# DoorModule_V2_0.net
KiCad netlist of a schematic drawn in EAGLE
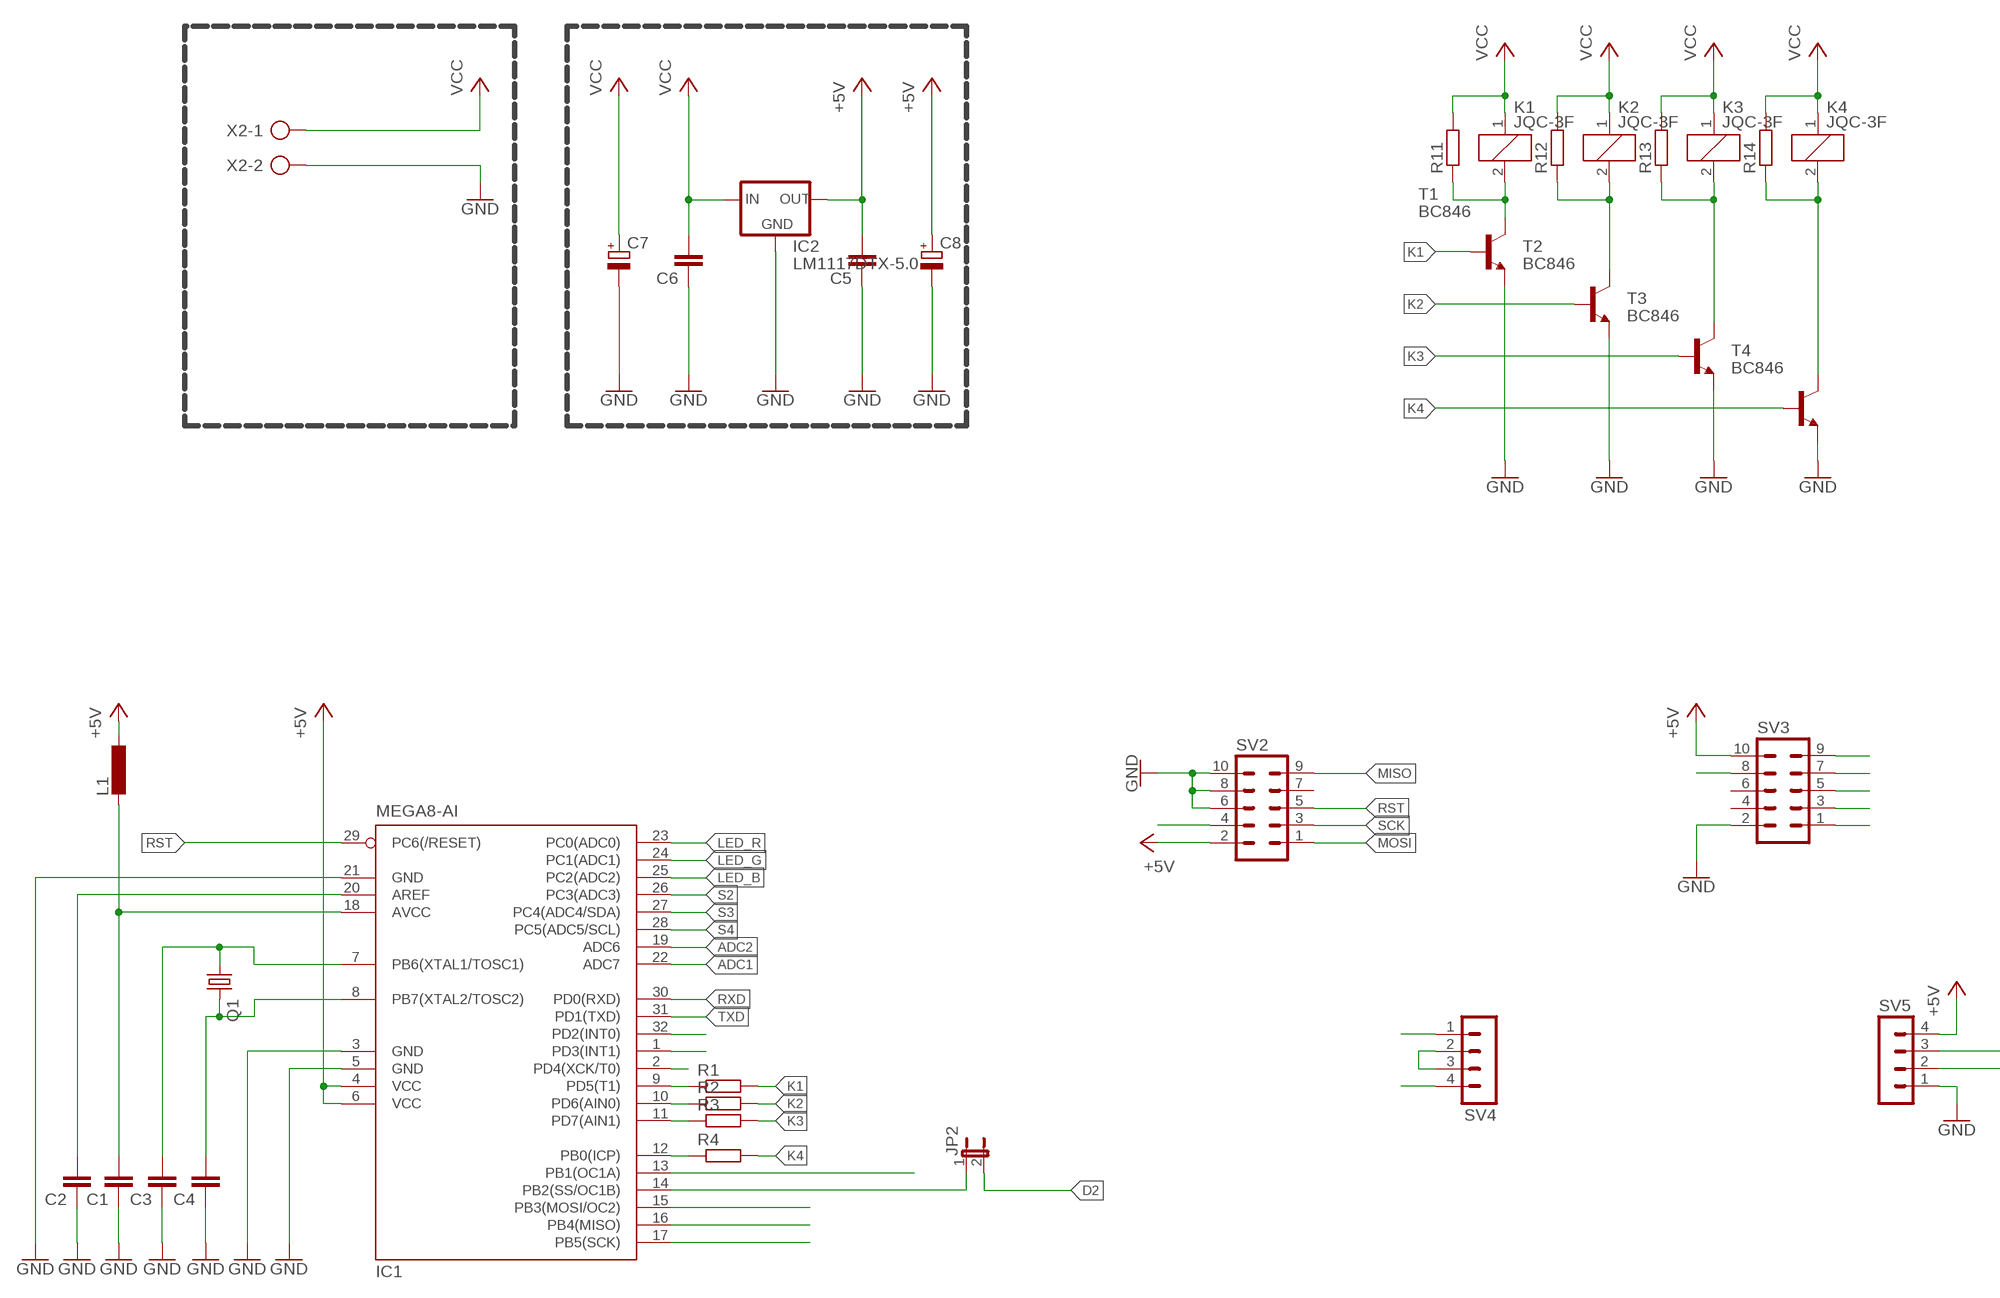
[diagram p0: schematic, sheet 1, part 1 of 2]
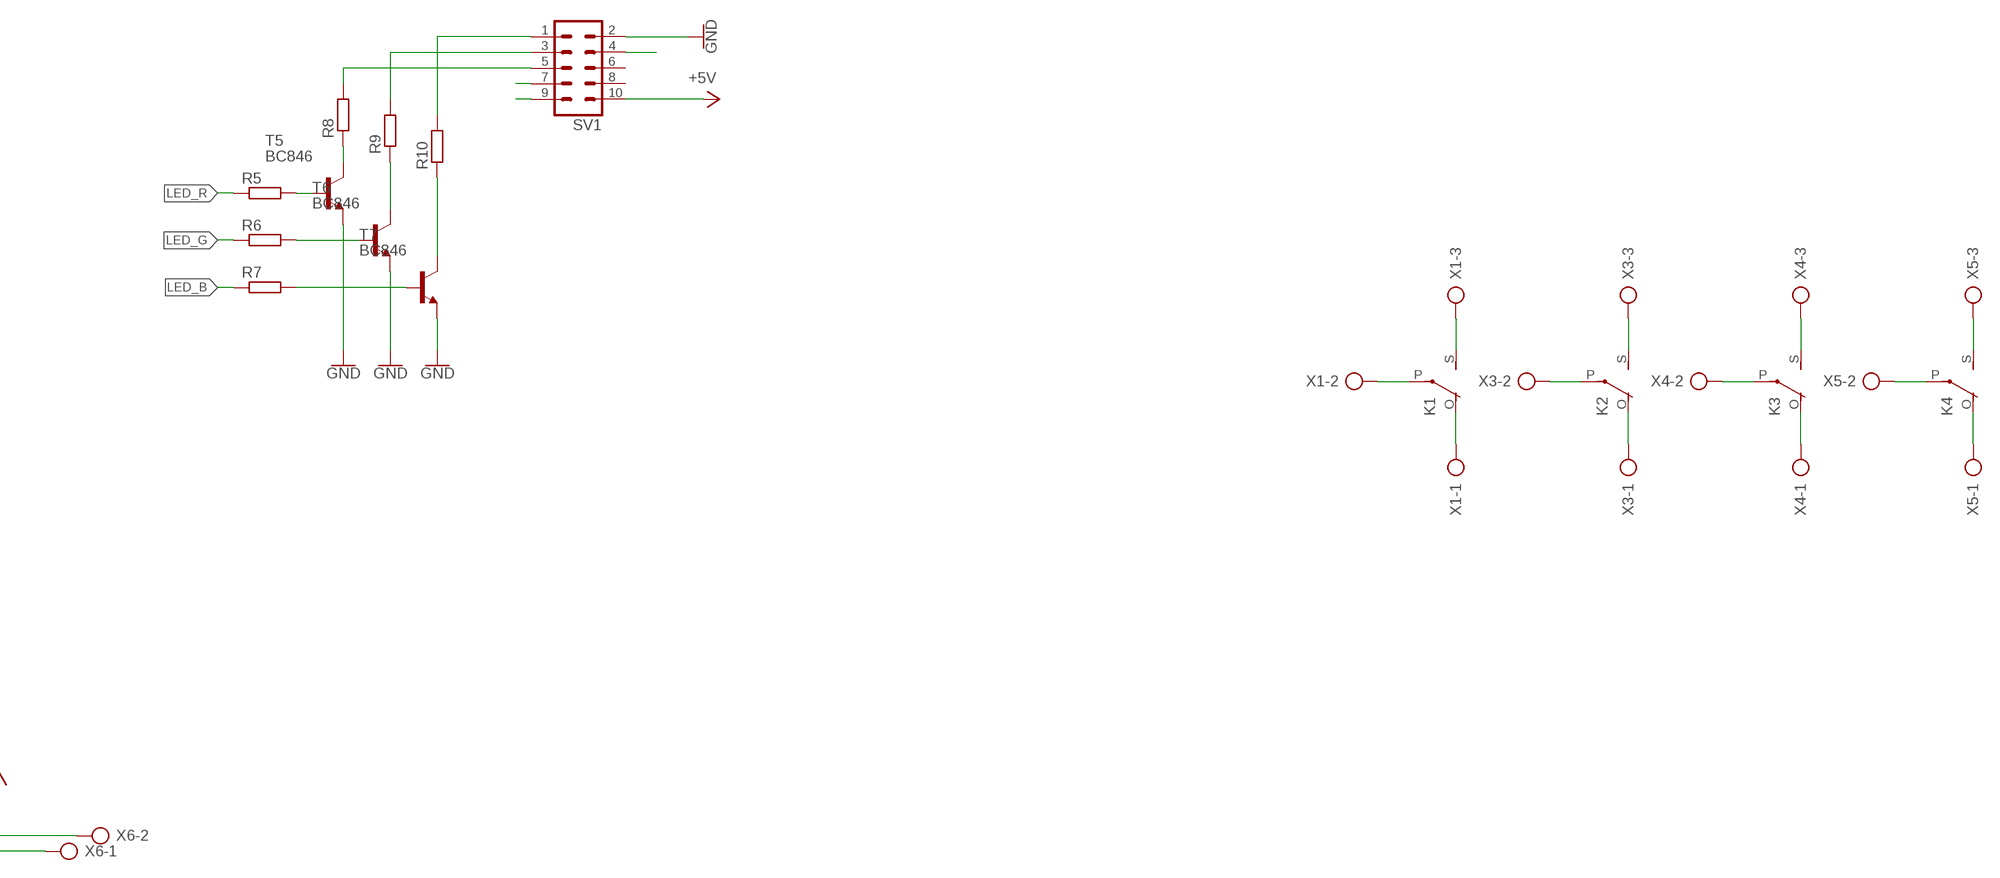
[diagram p1: schematic, sheet 1, part 2 of 2]

(export (version "E")
  (design (tool "Eeschema 10.0.6"))
  (components
    (comp (ref "C1")
      (value "C-EUC0805")
      (footprint "eagle-import:C0805")
      (libsource (lib "eagle-import") (part "C-EUC0805"))
    )
    (comp (ref "C2")
      (value "C-EUC0805")
      (footprint "eagle-import:C0805")
      (libsource (lib "eagle-import") (part "C-EUC0805"))
    )
    (comp (ref "C3")
      (value "C-EUC0805")
      (footprint "eagle-import:C0805")
      (libsource (lib "eagle-import") (part "C-EUC0805"))
    )
    (comp (ref "C4")
      (value "C-EUC0805")
      (footprint "eagle-import:C0805")
      (libsource (lib "eagle-import") (part "C-EUC0805"))
    )
    (comp (ref "C5")
      (value "C-EUC0805")
      (footprint "eagle-import:C0805")
      (libsource (lib "eagle-import") (part "C-EUC0805"))
    )
    (comp (ref "C6")
      (value "C-EUC0805")
      (footprint "eagle-import:C0805")
      (libsource (lib "eagle-import") (part "C-EUC0805"))
    )
    (comp (ref "C7")
      (value "CPOL-EUE2.5-7")
      (footprint "eagle-import:E2,5-7")
      (libsource (lib "eagle-import") (part "CPOL-EUE2.5-7"))
    )
    (comp (ref "C8")
      (value "CPOL-EUE2.5-7")
      (footprint "eagle-import:E2,5-7")
      (libsource (lib "eagle-import") (part "CPOL-EUE2.5-7"))
    )
    (comp (ref "IC1")
      (value "MEGA8-AI")
      (footprint "eagle-import:TQFP32-08")
      (fields (field (name "MPN") "ATMEGA8-16AU"))
      (libsource (lib "eagle-import") (part "MEGA8-AI"))
    )
    (comp (ref "IC2")
      (value "LM1117DTX-5.0")
      (footprint "eagle-import:TO252")
      (libsource (lib "eagle-import") (part "LM1117DTX-5.0"))
    )
    (comp (ref "JP2")
      (value "JP1E")
      (footprint "eagle-import:JP1")
      (libsource (lib "eagle-import") (part "JP1E"))
    )
    (comp (ref "K1")
      (value "JQC-3F")
      (footprint "eagle-import:G5LE")
      (libsource (lib "eagle-import") (part "G5LE"))
    )
    (comp (ref "K2")
      (value "JQC-3F")
      (footprint "eagle-import:G5LE")
      (libsource (lib "eagle-import") (part "G5LE"))
    )
    (comp (ref "K3")
      (value "JQC-3F")
      (footprint "eagle-import:G5LE")
      (libsource (lib "eagle-import") (part "G5LE"))
    )
    (comp (ref "K4")
      (value "JQC-3F")
      (footprint "eagle-import:G5LE")
      (libsource (lib "eagle-import") (part "G5LE"))
    )
    (comp (ref "L1")
      (value "L-EU0204/7")
      (footprint "eagle-import:0204_7")
      (libsource (lib "eagle-import") (part "L-EU0204/7"))
    )
    (comp (ref "Q1")
      (value "CRYSTALHC49U-V")
      (footprint "eagle-import:HC49U-V")
      (libsource (lib "eagle-import") (part "CRYSTALHC49U-V"))
    )
    (comp (ref "R1")
      (value "R-EU_R0805")
      (footprint "eagle-import:R0805")
      (libsource (lib "eagle-import") (part "R-EU_R0805"))
    )
    (comp (ref "R2")
      (value "R-EU_R0805")
      (footprint "eagle-import:R0805")
      (libsource (lib "eagle-import") (part "R-EU_R0805"))
    )
    (comp (ref "R3")
      (value "R-EU_R0805")
      (footprint "eagle-import:R0805")
      (libsource (lib "eagle-import") (part "R-EU_R0805"))
    )
    (comp (ref "R4")
      (value "R-EU_R0805")
      (footprint "eagle-import:R0805")
      (libsource (lib "eagle-import") (part "R-EU_R0805"))
    )
    (comp (ref "R5")
      (value "R-EU_R0805")
      (footprint "eagle-import:R0805")
      (libsource (lib "eagle-import") (part "R-EU_R0805"))
    )
    (comp (ref "R6")
      (value "R-EU_R0805")
      (footprint "eagle-import:R0805")
      (libsource (lib "eagle-import") (part "R-EU_R0805"))
    )
    (comp (ref "R7")
      (value "R-EU_R0805")
      (footprint "eagle-import:R0805")
      (libsource (lib "eagle-import") (part "R-EU_R0805"))
    )
    (comp (ref "R8")
      (value "R-EU_0204/7")
      (footprint "eagle-import:0204_7")
      (libsource (lib "eagle-import") (part "R-EU_0204/7"))
    )
    (comp (ref "R9")
      (value "R-EU_0204/7")
      (footprint "eagle-import:0204_7")
      (libsource (lib "eagle-import") (part "R-EU_0204/7"))
    )
    (comp (ref "R10")
      (value "R-EU_R0805")
      (footprint "eagle-import:R0805")
      (libsource (lib "eagle-import") (part "R-EU_R0805"))
    )
    (comp (ref "R11")
      (value "R-EU_R0805")
      (footprint "eagle-import:R0805")
      (libsource (lib "eagle-import") (part "R-EU_R0805"))
    )
    (comp (ref "R12")
      (value "R-EU_R0805")
      (footprint "eagle-import:R0805")
      (libsource (lib "eagle-import") (part "R-EU_R0805"))
    )
    (comp (ref "R13")
      (value "R-EU_R0805")
      (footprint "eagle-import:R0805")
      (libsource (lib "eagle-import") (part "R-EU_R0805"))
    )
    (comp (ref "R14")
      (value "R-EU_R0805")
      (footprint "eagle-import:R0805")
      (libsource (lib "eagle-import") (part "R-EU_R0805"))
    )
    (comp (ref "SV1")
      (value "ML10L")
      (footprint "eagle-import:ML10L")
      (libsource (lib "eagle-import") (part "ML10L"))
    )
    (comp (ref "SV2")
      (value "ML10L")
      (footprint "eagle-import:ML10L")
      (libsource (lib "eagle-import") (part "ML10L"))
    )
    (comp (ref "SV3")
      (value "ML10L")
      (footprint "eagle-import:ML10L")
      (libsource (lib "eagle-import") (part "ML10L"))
    )
    (comp (ref "SV4")
      (value "MA04-1")
      (footprint "eagle-import:MA04-1")
      (libsource (lib "eagle-import") (part "MA04-1"))
    )
    (comp (ref "SV5")
      (value "MA04-1")
      (footprint "eagle-import:MA04-1")
      (libsource (lib "eagle-import") (part "MA04-1"))
    )
    (comp (ref "T1")
      (value "BC846")
      (footprint "eagle-import:SOT23")
      (libsource (lib "eagle-import") (part "BC846"))
    )
    (comp (ref "T2")
      (value "BC846")
      (footprint "eagle-import:SOT23")
      (libsource (lib "eagle-import") (part "BC846"))
    )
    (comp (ref "T3")
      (value "BC846")
      (footprint "eagle-import:SOT23")
      (libsource (lib "eagle-import") (part "BC846"))
    )
    (comp (ref "T4")
      (value "BC846")
      (footprint "eagle-import:SOT23")
      (libsource (lib "eagle-import") (part "BC846"))
    )
    (comp (ref "T5")
      (value "BC846")
      (footprint "eagle-import:SOT23")
      (libsource (lib "eagle-import") (part "BC846"))
    )
    (comp (ref "T6")
      (value "BC846")
      (footprint "eagle-import:SOT23")
      (libsource (lib "eagle-import") (part "BC846"))
    )
    (comp (ref "T7")
      (value "BC846")
      (footprint "eagle-import:SOT23")
      (libsource (lib "eagle-import") (part "BC846"))
    )
    (comp (ref "X1")
      (value "AK300/3")
      (footprint "eagle-import:AK300_3")
      (libsource (lib "eagle-import") (part "AK300/3"))
    )
    (comp (ref "X2")
      (value "AK300/2")
      (footprint "eagle-import:AK300_2")
      (libsource (lib "eagle-import") (part "AK300/2"))
    )
    (comp (ref "X3")
      (value "AK300/3")
      (footprint "eagle-import:AK300_3")
      (libsource (lib "eagle-import") (part "AK300/3"))
    )
    (comp (ref "X4")
      (value "AK300/3")
      (footprint "eagle-import:AK300_3")
      (libsource (lib "eagle-import") (part "AK300/3"))
    )
    (comp (ref "X5")
      (value "AK300/3")
      (footprint "eagle-import:AK300_3")
      (libsource (lib "eagle-import") (part "AK300/3"))
    )
    (comp (ref "X6")
      (value "AK300/2")
      (footprint "eagle-import:AK300_2")
      (libsource (lib "eagle-import") (part "AK300/2"))
    )
  )
  (nets
    (net (code "1") (name "+5V") (class "Default")
      (node (ref "C5") (pin "2") (pinfunction "2_2") (pintype "passive"))
      (node (ref "C8") (pin "+") (pinfunction "+_+") (pintype "passive"))
      (node (ref "IC1") (pin "4") (pinfunction "VCC_4") (pintype "power_in"))
      (node (ref "IC1") (pin "6") (pinfunction "VCC_6") (pintype "power_in"))
      (node (ref "IC2") (pin "TAB") (pinfunction "OUT_TAB") (pintype "passive"))
      (node (ref "L1") (pin "1") (pinfunction "1_1") (pintype "passive"))
      (node (ref "SV1") (pin "10") (pinfunction "10_10") (pintype "passive"))
      (node (ref "SV2") (pin "2") (pinfunction "2_2") (pintype "passive"))
      (node (ref "SV3") (pin "10") (pinfunction "10_10") (pintype "passive"))
      (node (ref "SV5") (pin "4") (pinfunction "4_4") (pintype "passive"))
    )
    (net (code "2") (name "/D1") (class "Default")
      (node (ref "IC1") (pin "13") (pinfunction "PB1(OC1A)_13") (pintype "bidirectional"))
      (node (ref "SV1") (pin "4") (pinfunction "4_4") (pintype "passive"))
    )
    (net (code "3") (name "/INT0") (class "Default")
      (node (ref "IC1") (pin "32") (pinfunction "PD2(INT0)_32") (pintype "bidirectional"))
      (node (ref "SV3") (pin "9") (pinfunction "9_9") (pintype "passive"))
    )
    (net (code "4") (name "/INT1") (class "Default")
      (node (ref "IC1") (pin "1") (pinfunction "PD3(INT1)_1") (pintype "bidirectional"))
      (node (ref "SV3") (pin "8") (pinfunction "8_8") (pintype "passive"))
    )
    (net (code "5") (name "/RS") (class "Default")
      (node (ref "IC1") (pin "2") (pinfunction "PD4(XCK/T0)_2") (pintype "bidirectional"))
      (node (ref "SV4") (pin "2") (pinfunction "2_2") (pintype "passive"))
      (node (ref "SV4") (pin "3") (pinfunction "3_3") (pintype "passive"))
    )
    (net (code "6") (name "ADC1") (class "Default")
      (node (ref "IC1") (pin "22") (pinfunction "ADC7_22") (pintype "bidirectional"))
      (node (ref "SV3") (pin "1") (pinfunction "1_1") (pintype "passive"))
    )
    (net (code "7") (name "ADC2") (class "Default")
      (node (ref "IC1") (pin "19") (pinfunction "ADC6_19") (pintype "bidirectional"))
      (node (ref "SV3") (pin "3") (pinfunction "3_3") (pintype "passive"))
    )
    (net (code "8") (name "D2") (class "Default")
      (node (ref "JP2") (pin "2") (pinfunction "2_2") (pintype "passive"))
      (node (ref "SV2") (pin "4") (pinfunction "4_4") (pintype "passive"))
    )
    (net (code "9") (name "GND") (class "Default")
      (node (ref "C1") (pin "1") (pinfunction "1_1") (pintype "passive"))
      (node (ref "C2") (pin "1") (pinfunction "1_1") (pintype "passive"))
      (node (ref "C3") (pin "1") (pinfunction "1_1") (pintype "passive"))
      (node (ref "C4") (pin "1") (pinfunction "1_1") (pintype "passive"))
      (node (ref "C5") (pin "1") (pinfunction "1_1") (pintype "passive"))
      (node (ref "C6") (pin "1") (pinfunction "1_1") (pintype "passive"))
      (node (ref "C7") (pin "-") (pinfunction "-_-") (pintype "passive"))
      (node (ref "C8") (pin "-") (pinfunction "-_-") (pintype "passive"))
      (node (ref "IC1") (pin "21") (pinfunction "GND_21") (pintype "power_in"))
      (node (ref "IC1") (pin "3") (pinfunction "GND_3") (pintype "power_in"))
      (node (ref "IC1") (pin "5") (pinfunction "GND_5") (pintype "power_in"))
      (node (ref "IC2") (pin "1") (pinfunction "GND_1") (pintype "input"))
      (node (ref "SV1") (pin "2") (pinfunction "2_2") (pintype "passive"))
      (node (ref "SV2") (pin "10") (pinfunction "10_10") (pintype "passive"))
      (node (ref "SV2") (pin "6") (pinfunction "6_6") (pintype "passive"))
      (node (ref "SV2") (pin "8") (pinfunction "8_8") (pintype "passive"))
      (node (ref "SV3") (pin "2") (pinfunction "2_2") (pintype "passive"))
      (node (ref "SV5") (pin "1") (pinfunction "1_1") (pintype "passive"))
      (node (ref "T1") (pin "2") (pinfunction "E_2") (pintype "passive"))
      (node (ref "T2") (pin "2") (pinfunction "E_2") (pintype "passive"))
      (node (ref "T3") (pin "2") (pinfunction "E_2") (pintype "passive"))
      (node (ref "T4") (pin "2") (pinfunction "E_2") (pintype "passive"))
      (node (ref "T5") (pin "2") (pinfunction "E_2") (pintype "passive"))
      (node (ref "T6") (pin "2") (pinfunction "E_2") (pintype "passive"))
      (node (ref "T7") (pin "2") (pinfunction "E_2") (pintype "passive"))
      (node (ref "X2") (pin "2") (pinfunction "KL_2") (pintype "passive"))
    )
    (net (code "10") (name "K1") (class "Default")
      (node (ref "R1") (pin "2") (pinfunction "2_2") (pintype "passive"))
      (node (ref "T1") (pin "1") (pinfunction "B_1") (pintype "passive"))
    )
    (net (code "11") (name "K2") (class "Default")
      (node (ref "R2") (pin "2") (pinfunction "2_2") (pintype "passive"))
      (node (ref "T2") (pin "1") (pinfunction "B_1") (pintype "passive"))
    )
    (net (code "12") (name "K3") (class "Default")
      (node (ref "R3") (pin "2") (pinfunction "2_2") (pintype "passive"))
      (node (ref "T3") (pin "1") (pinfunction "B_1") (pintype "passive"))
    )
    (net (code "13") (name "K4") (class "Default")
      (node (ref "R4") (pin "2") (pinfunction "2_2") (pintype "passive"))
      (node (ref "T4") (pin "1") (pinfunction "B_1") (pintype "passive"))
    )
    (net (code "14") (name "LED_B") (class "Default")
      (node (ref "IC1") (pin "25") (pinfunction "PC2(ADC2)_25") (pintype "bidirectional"))
      (node (ref "R7") (pin "1") (pinfunction "1_1") (pintype "passive"))
    )
    (net (code "15") (name "LED_G") (class "Default")
      (node (ref "IC1") (pin "24") (pinfunction "PC1(ADC1)_24") (pintype "bidirectional"))
      (node (ref "R6") (pin "1") (pinfunction "1_1") (pintype "passive"))
    )
    (net (code "16") (name "LED_R") (class "Default")
      (node (ref "IC1") (pin "23") (pinfunction "PC0(ADC0)_23") (pintype "bidirectional"))
      (node (ref "R5") (pin "1") (pinfunction "1_1") (pintype "passive"))
    )
    (net (code "17") (name "MISO") (class "Default")
      (node (ref "IC1") (pin "16") (pinfunction "PB4(MISO)_16") (pintype "bidirectional"))
      (node (ref "SV2") (pin "9") (pinfunction "9_9") (pintype "passive"))
    )
    (net (code "18") (name "MOSI") (class "Default")
      (node (ref "IC1") (pin "15") (pinfunction "PB3(MOSI/OC2)_15") (pintype "bidirectional"))
      (node (ref "SV2") (pin "1") (pinfunction "1_1") (pintype "passive"))
    )
    (net (code "19") (name "Net-(IC1-AREF)") (class "Default")
      (node (ref "C2") (pin "2") (pinfunction "2_2") (pintype "passive"))
      (node (ref "IC1") (pin "20") (pinfunction "AREF_20") (pintype "passive"))
    )
    (net (code "20") (name "Net-(IC1-AVCC)") (class "Default")
      (node (ref "C1") (pin "2") (pinfunction "2_2") (pintype "passive"))
      (node (ref "IC1") (pin "18") (pinfunction "AVCC_18") (pintype "power_in"))
      (node (ref "L1") (pin "2") (pinfunction "2_2") (pintype "passive"))
    )
    (net (code "21") (name "Net-(IC1-PB0(ICP))") (class "Default")
      (node (ref "IC1") (pin "12") (pinfunction "PB0(ICP)_12") (pintype "bidirectional"))
      (node (ref "R4") (pin "1") (pinfunction "1_1") (pintype "passive"))
    )
    (net (code "22") (name "Net-(IC1-PB2(SS{slash}OC1B))") (class "Default")
      (node (ref "IC1") (pin "14") (pinfunction "PB2(SS/OC1B)_14") (pintype "bidirectional"))
      (node (ref "JP2") (pin "1") (pinfunction "1_1") (pintype "passive"))
    )
    (net (code "23") (name "Net-(IC1-PB6(XTAL1{slash}TOSC1))") (class "Default")
      (node (ref "C3") (pin "2") (pinfunction "2_2") (pintype "passive"))
      (node (ref "IC1") (pin "7") (pinfunction "PB6(XTAL1/TOSC1)_7") (pintype "bidirectional"))
      (node (ref "Q1") (pin "1") (pinfunction "1_1") (pintype "passive"))
    )
    (net (code "24") (name "Net-(IC1-PB7(XTAL2{slash}TOSC2))") (class "Default")
      (node (ref "C4") (pin "2") (pinfunction "2_2") (pintype "passive"))
      (node (ref "IC1") (pin "8") (pinfunction "PB7(XTAL2/TOSC2)_8") (pintype "bidirectional"))
      (node (ref "Q1") (pin "2") (pinfunction "2_2") (pintype "passive"))
    )
    (net (code "25") (name "Net-(IC1-PD5(T1))") (class "Default")
      (node (ref "IC1") (pin "9") (pinfunction "PD5(T1)_9") (pintype "bidirectional"))
      (node (ref "R1") (pin "1") (pinfunction "1_1") (pintype "passive"))
    )
    (net (code "26") (name "Net-(IC1-PD6(AIN0))") (class "Default")
      (node (ref "IC1") (pin "10") (pinfunction "PD6(AIN0)_10") (pintype "bidirectional"))
      (node (ref "R2") (pin "1") (pinfunction "1_1") (pintype "passive"))
    )
    (net (code "27") (name "Net-(IC1-PD7(AIN1))") (class "Default")
      (node (ref "IC1") (pin "11") (pinfunction "PD7(AIN1)_11") (pintype "bidirectional"))
      (node (ref "R3") (pin "1") (pinfunction "1_1") (pintype "passive"))
    )
    (net (code "28") (name "Net-(R8-Pad2)") (class "Default")
      (node (ref "R8") (pin "2") (pinfunction "2_2") (pintype "passive"))
      (node (ref "SV1") (pin "5") (pinfunction "5_5") (pintype "passive"))
    )
    (net (code "29") (name "Net-(R9-Pad2)") (class "Default")
      (node (ref "R9") (pin "2") (pinfunction "2_2") (pintype "passive"))
      (node (ref "SV1") (pin "3") (pinfunction "3_3") (pintype "passive"))
    )
    (net (code "30") (name "Net-(R10-Pad2)") (class "Default")
      (node (ref "R10") (pin "2") (pinfunction "2_2") (pintype "passive"))
      (node (ref "SV1") (pin "1") (pinfunction "1_1") (pintype "passive"))
    )
    (net (code "31") (name "Net-(T1-C)") (class "Default")
      (node (ref "K1") (pin "2") (pinfunction "2_2") (pintype "passive"))
      (node (ref "R11") (pin "1") (pinfunction "1_1") (pintype "passive"))
      (node (ref "T1") (pin "3") (pinfunction "C_3") (pintype "passive"))
    )
    (net (code "32") (name "Net-(T2-C)") (class "Default")
      (node (ref "K2") (pin "2") (pinfunction "2_2") (pintype "passive"))
      (node (ref "R12") (pin "1") (pinfunction "1_1") (pintype "passive"))
      (node (ref "T2") (pin "3") (pinfunction "C_3") (pintype "passive"))
    )
    (net (code "33") (name "Net-(T3-C)") (class "Default")
      (node (ref "K3") (pin "2") (pinfunction "2_2") (pintype "passive"))
      (node (ref "R13") (pin "1") (pinfunction "1_1") (pintype "passive"))
      (node (ref "T3") (pin "3") (pinfunction "C_3") (pintype "passive"))
    )
    (net (code "34") (name "Net-(T4-C)") (class "Default")
      (node (ref "K4") (pin "2") (pinfunction "2_2") (pintype "passive"))
      (node (ref "R14") (pin "1") (pinfunction "1_1") (pintype "passive"))
      (node (ref "T4") (pin "3") (pinfunction "C_3") (pintype "passive"))
    )
    (net (code "35") (name "Net-(T5-B)") (class "Default")
      (node (ref "R5") (pin "2") (pinfunction "2_2") (pintype "passive"))
      (node (ref "T5") (pin "1") (pinfunction "B_1") (pintype "passive"))
    )
    (net (code "36") (name "Net-(T5-C)") (class "Default")
      (node (ref "R8") (pin "1") (pinfunction "1_1") (pintype "passive"))
      (node (ref "T5") (pin "3") (pinfunction "C_3") (pintype "passive"))
    )
    (net (code "37") (name "Net-(T6-B)") (class "Default")
      (node (ref "R6") (pin "2") (pinfunction "2_2") (pintype "passive"))
      (node (ref "T6") (pin "1") (pinfunction "B_1") (pintype "passive"))
    )
    (net (code "38") (name "Net-(T6-C)") (class "Default")
      (node (ref "R9") (pin "1") (pinfunction "1_1") (pintype "passive"))
      (node (ref "T6") (pin "3") (pinfunction "C_3") (pintype "passive"))
    )
    (net (code "39") (name "Net-(T7-B)") (class "Default")
      (node (ref "R7") (pin "2") (pinfunction "2_2") (pintype "passive"))
      (node (ref "T7") (pin "1") (pinfunction "B_1") (pintype "passive"))
    )
    (net (code "40") (name "Net-(T7-C)") (class "Default")
      (node (ref "R10") (pin "1") (pinfunction "1_1") (pintype "passive"))
      (node (ref "T7") (pin "3") (pinfunction "C_3") (pintype "passive"))
    )
    (net (code "41") (name "Net-(X1A-KL)") (class "Default")
      (node (ref "K1") (pin "O") (pinfunction "O_O") (pintype "passive"))
      (node (ref "X1") (pin "1") (pinfunction "KL_1") (pintype "passive"))
    )
    (net (code "42") (name "Net-(X1B-KL)") (class "Default")
      (node (ref "K1") (pin "P") (pinfunction "P_P") (pintype "passive"))
      (node (ref "X1") (pin "2") (pinfunction "KL_2") (pintype "passive"))
    )
    (net (code "43") (name "Net-(X1C-KL)") (class "Default")
      (node (ref "K1") (pin "S") (pinfunction "S_S") (pintype "passive"))
      (node (ref "X1") (pin "3") (pinfunction "KL_3") (pintype "passive"))
    )
    (net (code "44") (name "Net-(X3A-KL)") (class "Default")
      (node (ref "K2") (pin "O") (pinfunction "O_O") (pintype "passive"))
      (node (ref "X3") (pin "1") (pinfunction "KL_1") (pintype "passive"))
    )
    (net (code "45") (name "Net-(X3B-KL)") (class "Default")
      (node (ref "K2") (pin "P") (pinfunction "P_P") (pintype "passive"))
      (node (ref "X3") (pin "2") (pinfunction "KL_2") (pintype "passive"))
    )
    (net (code "46") (name "Net-(X3C-KL)") (class "Default")
      (node (ref "K2") (pin "S") (pinfunction "S_S") (pintype "passive"))
      (node (ref "X3") (pin "3") (pinfunction "KL_3") (pintype "passive"))
    )
    (net (code "47") (name "Net-(X4A-KL)") (class "Default")
      (node (ref "K3") (pin "O") (pinfunction "O_O") (pintype "passive"))
      (node (ref "X4") (pin "1") (pinfunction "KL_1") (pintype "passive"))
    )
    (net (code "48") (name "Net-(X4B-KL)") (class "Default")
      (node (ref "K3") (pin "P") (pinfunction "P_P") (pintype "passive"))
      (node (ref "X4") (pin "2") (pinfunction "KL_2") (pintype "passive"))
    )
    (net (code "49") (name "Net-(X4C-KL)") (class "Default")
      (node (ref "K3") (pin "S") (pinfunction "S_S") (pintype "passive"))
      (node (ref "X4") (pin "3") (pinfunction "KL_3") (pintype "passive"))
    )
    (net (code "50") (name "Net-(X5A-KL)") (class "Default")
      (node (ref "K4") (pin "O") (pinfunction "O_O") (pintype "passive"))
      (node (ref "X5") (pin "1") (pinfunction "KL_1") (pintype "passive"))
    )
    (net (code "51") (name "Net-(X5B-KL)") (class "Default")
      (node (ref "K4") (pin "P") (pinfunction "P_P") (pintype "passive"))
      (node (ref "X5") (pin "2") (pinfunction "KL_2") (pintype "passive"))
    )
    (net (code "52") (name "Net-(X5C-KL)") (class "Default")
      (node (ref "K4") (pin "S") (pinfunction "S_S") (pintype "passive"))
      (node (ref "X5") (pin "3") (pinfunction "KL_3") (pintype "passive"))
    )
    (net (code "53") (name "Net-(X6A-KL)") (class "Default")
      (node (ref "SV5") (pin "2") (pinfunction "2_2") (pintype "passive"))
      (node (ref "X6") (pin "1") (pinfunction "KL_1") (pintype "passive"))
    )
    (net (code "54") (name "Net-(X6B-KL)") (class "Default")
      (node (ref "SV5") (pin "3") (pinfunction "3_3") (pintype "passive"))
      (node (ref "X6") (pin "2") (pinfunction "KL_2") (pintype "passive"))
    )
    (net (code "55") (name "RST") (class "Default")
      (node (ref "IC1") (pin "29") (pinfunction "PC6(/RESET)_29") (pintype "bidirectional"))
      (node (ref "SV2") (pin "5") (pinfunction "5_5") (pintype "passive"))
    )
    (net (code "56") (name "RXD") (class "Default")
      (node (ref "IC1") (pin "30") (pinfunction "PD0(RXD)_30") (pintype "bidirectional"))
      (node (ref "SV4") (pin "1") (pinfunction "1_1") (pintype "passive"))
    )
    (net (code "57") (name "S2") (class "Default")
      (node (ref "IC1") (pin "26") (pinfunction "PC3(ADC3)_26") (pintype "bidirectional"))
      (node (ref "SV1") (pin "7") (pinfunction "7_7") (pintype "passive"))
    )
    (net (code "58") (name "S3") (class "Default")
      (node (ref "IC1") (pin "27") (pinfunction "PC4(ADC4/SDA)_27") (pintype "bidirectional"))
      (node (ref "SV3") (pin "5") (pinfunction "5_5") (pintype "passive"))
    )
    (net (code "59") (name "S4") (class "Default")
      (node (ref "IC1") (pin "28") (pinfunction "PC5(ADC5/SCL)_28") (pintype "bidirectional"))
      (node (ref "SV3") (pin "7") (pinfunction "7_7") (pintype "passive"))
    )
    (net (code "60") (name "SCK") (class "Default")
      (node (ref "IC1") (pin "17") (pinfunction "PB5(SCK)_17") (pintype "bidirectional"))
      (node (ref "SV2") (pin "3") (pinfunction "3_3") (pintype "passive"))
    )
    (net (code "61") (name "TXD") (class "Default")
      (node (ref "IC1") (pin "31") (pinfunction "PD1(TXD)_31") (pintype "bidirectional"))
      (node (ref "SV4") (pin "4") (pinfunction "4_4") (pintype "passive"))
    )
    (net (code "62") (name "VCC") (class "Default")
      (node (ref "C6") (pin "2") (pinfunction "2_2") (pintype "passive"))
      (node (ref "C7") (pin "+") (pinfunction "+_+") (pintype "passive"))
      (node (ref "IC2") (pin "2") (pinfunction "IN_2") (pintype "input"))
      (node (ref "K1") (pin "1") (pinfunction "1_1") (pintype "passive"))
      (node (ref "K2") (pin "1") (pinfunction "1_1") (pintype "passive"))
      (node (ref "K3") (pin "1") (pinfunction "1_1") (pintype "passive"))
      (node (ref "K4") (pin "1") (pinfunction "1_1") (pintype "passive"))
      (node (ref "R11") (pin "2") (pinfunction "2_2") (pintype "passive"))
      (node (ref "R12") (pin "2") (pinfunction "2_2") (pintype "passive"))
      (node (ref "R13") (pin "2") (pinfunction "2_2") (pintype "passive"))
      (node (ref "R14") (pin "2") (pinfunction "2_2") (pintype "passive"))
      (node (ref "X2") (pin "1") (pinfunction "KL_1") (pintype "passive"))
    )
    (net (code "63") (name "unconnected-(SV1-Pad6)") (class "Default")
      (node (ref "SV1") (pin "6") (pinfunction "6_6") (pintype "passive"))
    )
    (net (code "64") (name "unconnected-(SV1-Pad8)") (class "Default")
      (node (ref "SV1") (pin "8") (pinfunction "8_8") (pintype "passive"))
    )
    (net (code "65") (name "unconnected-(SV1-Pad9)") (class "Default")
      (node (ref "SV1") (pin "9") (pinfunction "9_9") (pintype "passive"))
    )
    (net (code "66") (name "unconnected-(SV2-Pad7)") (class "Default")
      (node (ref "SV2") (pin "7") (pinfunction "7_7") (pintype "passive"))
    )
    (net (code "67") (name "unconnected-(SV3-Pad4)") (class "Default")
      (node (ref "SV3") (pin "4") (pinfunction "4_4") (pintype "passive"))
    )
    (net (code "68") (name "unconnected-(SV3-Pad6)") (class "Default")
      (node (ref "SV3") (pin "6") (pinfunction "6_6") (pintype "passive"))
    )
  )
)
